# supply.net
KiCad netlist of a schematic drawn in Altium Designer
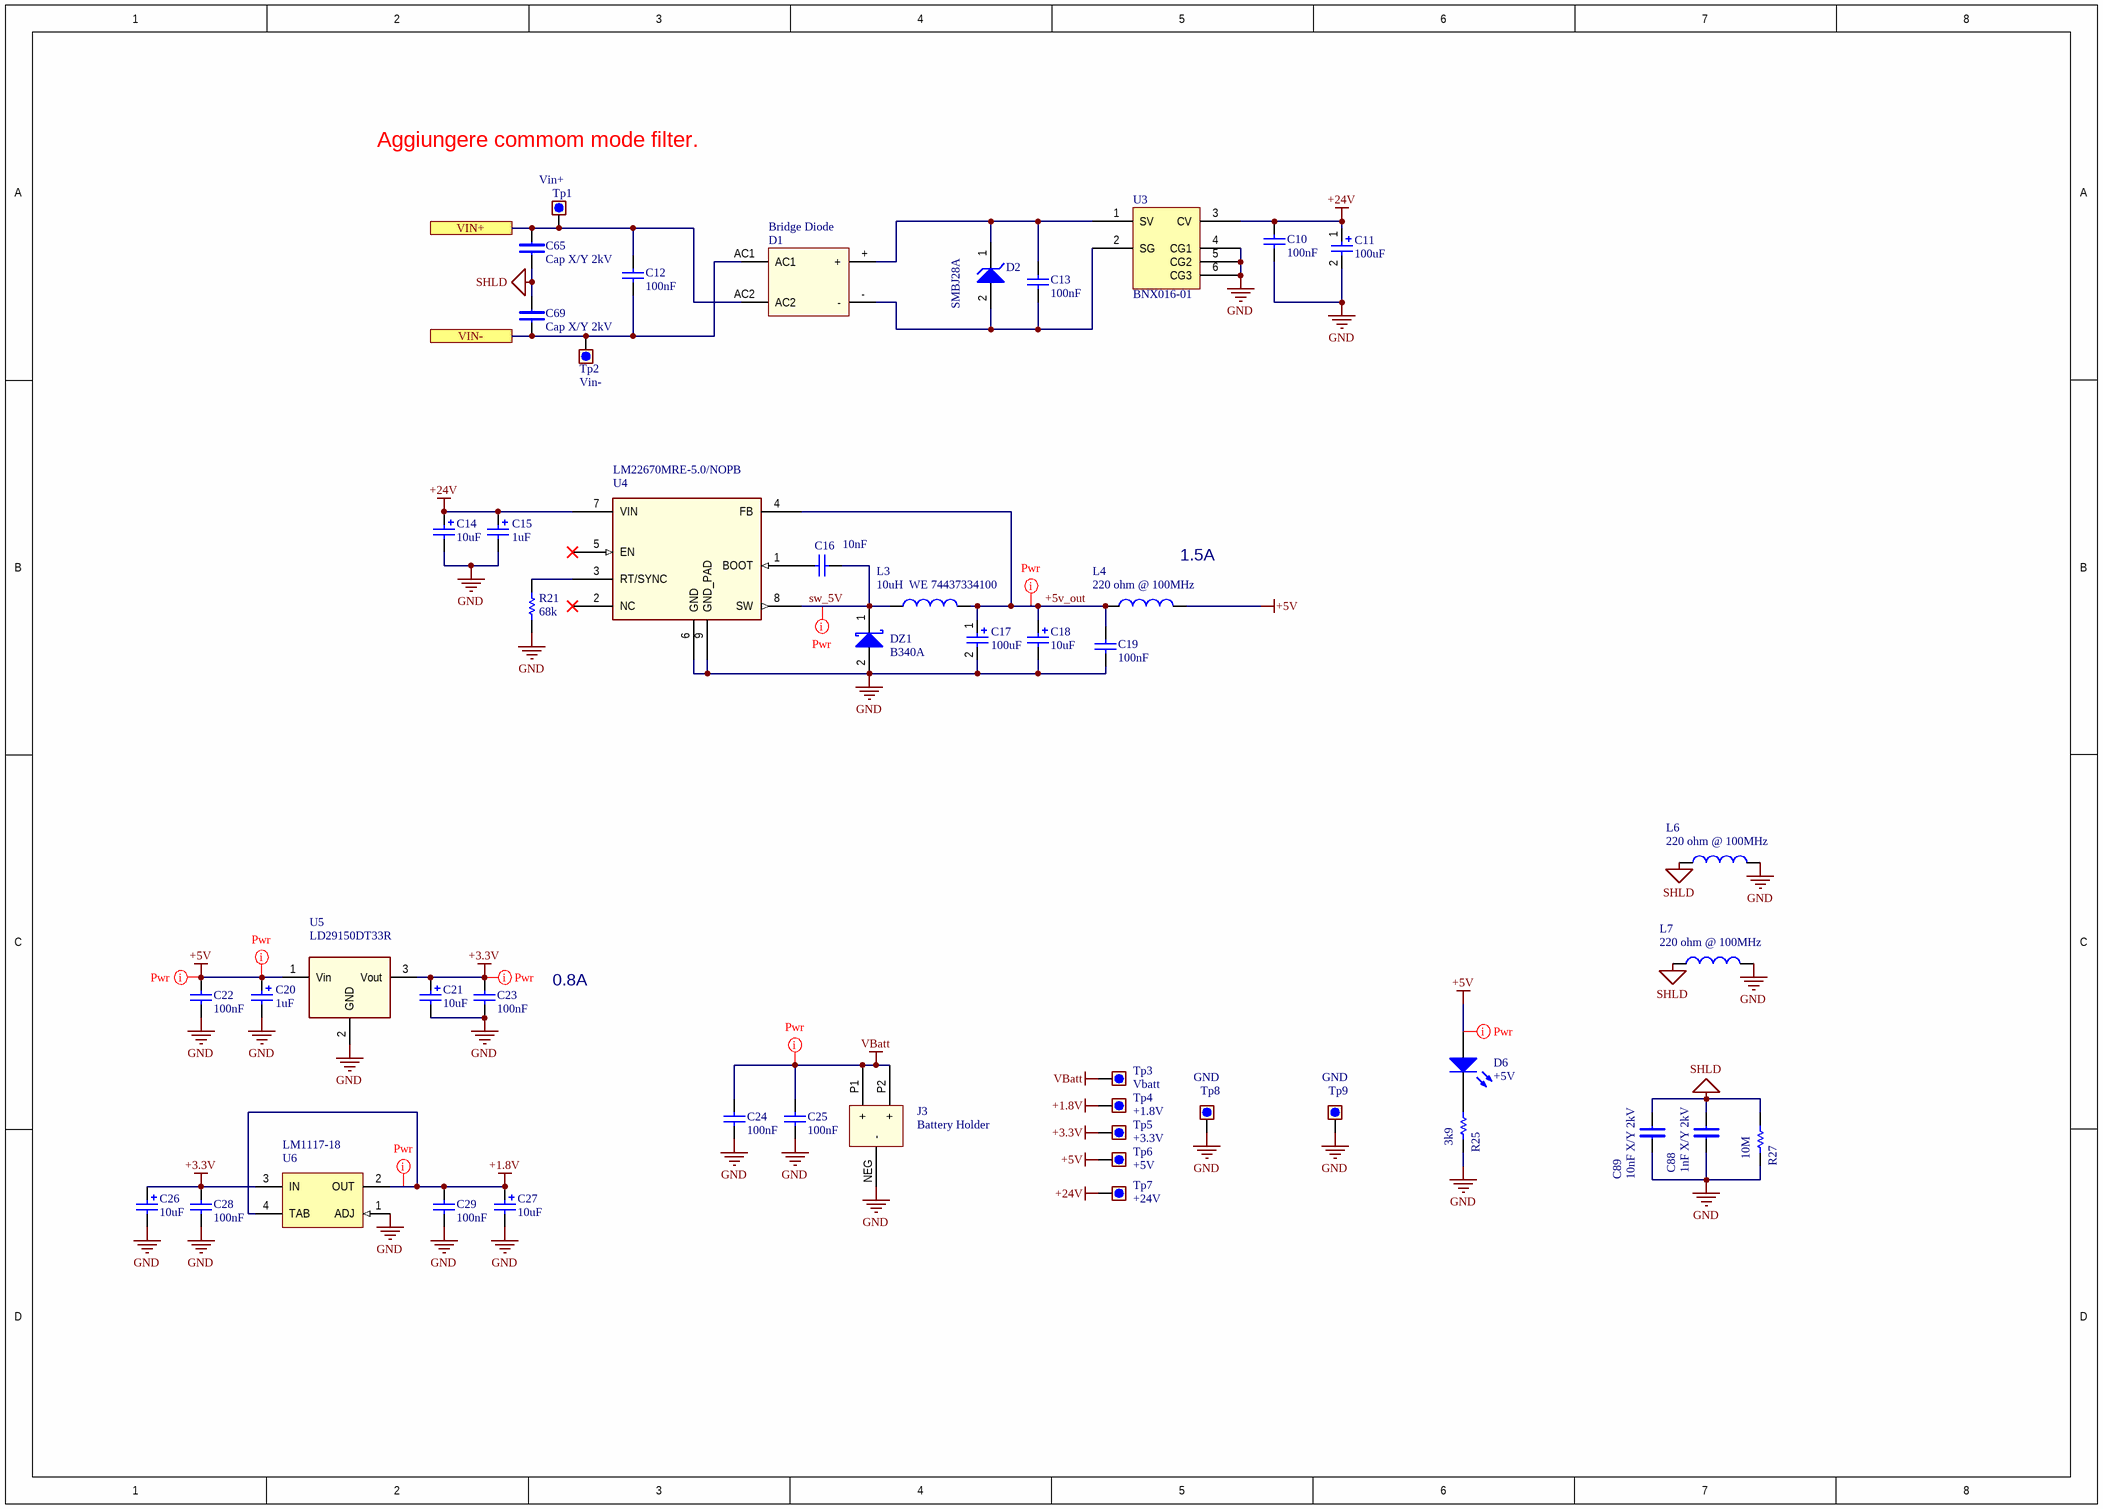
[diagram p0: supply.SchDoc]

(export (version "E")
  (design (tool "Eeschema 10.0.6"))
  (components
    (comp (ref "C10")
      (value "100nF")
      (footprint "0603_[1608]")
      (description "Ceramic X7R 50V")
      (fields (field (name "PUBLISHER") "Altium Limited"))
      (libsource (lib "DEVELER_Library") (part "Cap"))
    )
    (comp (ref "C11")
      (value "100uF")
      (footprint "CAP_6x6_D8_SMD")
      (description "EEEFK1H101P SMT 6x6 35V")
      (fields (field (name "PUBLISHER") "Altium Limited"))
      (libsource (lib "") (part "Cap Pol1_1"))
    )
    (comp (ref "C12")
      (value "100nF")
      (footprint "0603_[1608]")
      (description "Ceramic X7R 50V")
      (fields (field (name "PUBLISHER") "Altium Limited"))
      (libsource (lib "DEVELER_Library") (part "Cap"))
    )
    (comp (ref "C13")
      (value "100nF")
      (footprint "0603_[1608]")
      (description "Ceramic X7R 50V")
      (fields (field (name "PUBLISHER") "Altium Limited"))
      (libsource (lib "DEVELER_Library") (part "Cap"))
    )
    (comp (ref "C14")
      (value "10uF")
      (footprint "1206_[3216]")
      (description "Ceramic X5R 25V")
      (fields (field (name "PUBLISHER") "Altium Limited"))
      (libsource (lib "DEVELER_Library") (part "Cap Pol1"))
    )
    (comp (ref "C15")
      (value "1uF")
      (footprint "0805_[2012]")
      (description "Ceramic X7R 50V")
      (fields (field (name "PUBLISHER") "Altium Limited"))
      (libsource (lib "DEVELER_Library") (part "Cap Pol1"))
    )
    (comp (ref "C16")
      (value "10nF")
      (footprint "0603_[1608]")
      (description "Ceramic X7R 50V")
      (fields (field (name "PUBLISHER") "Altium Limited"))
      (libsource (lib "Miscellaneous Devices") (part "Cap"))
    )
    (comp (ref "C17")
      (value "100uF")
      (footprint "[7343]_CAP_TAN")
      (description "Tantalum 10V (T495D107K010ATE100)")
      (fields (field (name "PUBLISHER") "Altium Limited"))
      (libsource (lib "") (part "Cap Pol1_1"))
    )
    (comp (ref "C18")
      (value "10uF")
      (footprint "1206_[3216]")
      (description "Ceramic X5R 25V")
      (fields (field (name "PUBLISHER") "Altium Limited"))
      (libsource (lib "DEVELER_Library") (part "Cap Pol1"))
    )
    (comp (ref "C19")
      (value "100nF")
      (footprint "0603_[1608]")
      (description "Ceramic X7R 50V")
      (fields (field (name "PUBLISHER") "Altium Limited"))
      (libsource (lib "DEVELER_Library") (part "Cap"))
    )
    (comp (ref "C20")
      (value "1uF")
      (footprint "0805_[2012]")
      (description "Ceramic X7R 50V")
      (fields (field (name "PUBLISHER") "Altium Limited"))
      (libsource (lib "DEVELER_Library") (part "Cap Pol1"))
    )
    (comp (ref "C21")
      (value "10uF")
      (footprint "1206_[3216]")
      (description "Ceramic X5R 25V")
      (fields (field (name "PUBLISHER") "Altium Limited"))
      (libsource (lib "DEVELER_Library") (part "Cap Pol1"))
    )
    (comp (ref "C22")
      (value "100nF")
      (footprint "0603_[1608]")
      (description "Ceramic X7R 50V")
      (fields (field (name "PUBLISHER") "Altium Limited"))
      (libsource (lib "DEVELER_Library") (part "Cap"))
    )
    (comp (ref "C23")
      (value "100nF")
      (footprint "0603_[1608]")
      (description "Ceramic X7R 50V")
      (fields (field (name "PUBLISHER") "Altium Limited"))
      (libsource (lib "DEVELER_Library") (part "Cap"))
    )
    (comp (ref "C24")
      (value "100nF")
      (footprint "0603_[1608]")
      (description "Ceramic X7R 50V")
      (fields (field (name "PUBLISHER") "Altium Limited"))
      (libsource (lib "DEVELER_Library") (part "Cap"))
    )
    (comp (ref "C25")
      (value "100nF")
      (footprint "0603_[1608]")
      (description "Ceramic X7R 50V")
      (fields (field (name "PUBLISHER") "Altium Limited"))
      (libsource (lib "DEVELER_Library") (part "Cap"))
    )
    (comp (ref "C26")
      (value "10uF")
      (footprint "1206_[3216]")
      (description "Ceramic X5R 25V")
      (fields (field (name "PUBLISHER") "Altium Limited"))
      (libsource (lib "DEVELER_Library") (part "Cap Pol1"))
    )
    (comp (ref "C27")
      (value "10uF")
      (footprint "1206_[3216]")
      (description "Ceramic X5R 25V")
      (fields (field (name "PUBLISHER") "Altium Limited"))
      (libsource (lib "DEVELER_Library") (part "Cap Pol1"))
    )
    (comp (ref "C28")
      (value "100nF")
      (footprint "0603_[1608]")
      (description "Ceramic X7R 50V")
      (fields (field (name "PUBLISHER") "Altium Limited"))
      (libsource (lib "DEVELER_Library") (part "Cap"))
    )
    (comp (ref "C29")
      (value "100nF")
      (footprint "0603_[1608]")
      (description "Ceramic X7R 50V")
      (fields (field (name "PUBLISHER") "Altium Limited"))
      (libsource (lib "DEVELER_Library") (part "Cap"))
    )
    (comp (ref "C65")
      (value "Cap X/Y 2kV")
      (footprint "1808_[4520]")
      (description "Ceramic 1nF 1808 250VAC X7R X1/Y1 (Murata GA342DR7GF102KW)")
      (libsource (lib "develer_library") (part "cap_xy"))
    )
    (comp (ref "C69")
      (value "Cap X/Y 2kV")
      (footprint "1808_[4520]")
      (description "Ceramic 1nF 1808 250VAC X7R X1/Y1 (Murata GA342DR7GF102KW)")
      (libsource (lib "develer_library") (part "cap_xy"))
    )
    (comp (ref "C88")
      (value "1nF X/Y 2kV")
      (footprint "1808_[4520]")
      (description "Ceramic 250VAC X7R X1/Y1 (GA342DR7GF102KW)")
      (libsource (lib "develer_library") (part "cap_xy"))
    )
    (comp (ref "C89")
      (value "10nF X/Y 2kV")
      (footprint "2220_[5650]")
      (description "Ceramic 250VAC X7R X1/Y1 (GA355DR7GB103KY02L)")
      (libsource (lib "develer_library") (part "cap_xy"))
    )
    (comp (ref "D1")
      (value "Bridge Diode")
      (footprint "Diode_bridge_smd")
      (description "MBS4 (Farnell cod:4084985)")
      (libsource (lib "DEVELER_Library") (part "Diode_bridge2"))
    )
    (comp (ref "D2")
      (value "SMBJ28A")
      (footprint "DO214AA_K1-A2_SMB")
      (description "TVS Monodirectional")
      (fields (field (name "PUBLISHER") "Altium Limited"))
      (libsource (lib "DEVELER_Library") (part "D Zener"))
    )
    (comp (ref "D6")
      (value "+5V")
      (footprint "0603_[1608]_K2-A1_LED")
      (description "LED Green")
      (fields (field (name "PUBLISHER") "Altium Limited"))
      (libsource (lib "DEVELER_Library") (part "LED0"))
    )
    (comp (ref "DZ1")
      (value "B340A")
      (footprint "DO214AA_K1-A2_SMB")
      (description "Diode Schottky (STPS2L40U)")
      (fields (field (name "PUBLISHER") "Altium Limited"))
      (libsource (lib "Miscellaneous Devices") (part "D Schottky"))
    )
    (comp (ref "J3")
      (value "Battery Holder")
      (footprint "Battery_holder_16mm_thd")
      (description "CR1612/1616/1620/1632 (3013, Keystone)")
      (libsource (lib "DEVELER_Library") (part "Battery_holder_3002"))
    )
    (comp (ref "L3")
      (value "10uH  WE 74437334100")
      (footprint "WE-LHMI_5020")
      (description "SMD Shielded Tiny Power Inductor")
      (fields (field (name "PUBLISHER") "Altium Limited"))
      (libsource (lib "Miscellaneous Devices") (part "Inductor"))
    )
    (comp (ref "L4")
      (value "220 ohm @ 100MHz")
      (footprint "0805_[2012]")
      (description "WE 742792022")
      (libsource (lib "DEVELER_Library") (part "Ferrite Bead"))
    )
    (comp (ref "L6")
      (value "220 ohm @ 100MHz")
      (footprint "0805_[2012]")
      (description "WE 742792022")
      (libsource (lib "DEVELER_Library") (part "Ferrite Bead"))
    )
    (comp (ref "L7")
      (value "220 ohm @ 100MHz")
      (footprint "0805_[2012]")
      (description "WE 742792022")
      (libsource (lib "DEVELER_Library") (part "Ferrite Bead"))
    )
    (comp (ref "R21")
      (value "68k")
      (footprint "0603_[1608]")
      (description "Resistor")
      (libsource (lib "DEVELER_Library") (part "Res1"))
    )
    (comp (ref "R25")
      (value "3k9")
      (footprint "0603_[1608]")
      (description "Resistor")
      (libsource (lib "DEVELER_Library") (part "Res1"))
    )
    (comp (ref "R27")
      (value "10M")
      (footprint "1206_[3216]")
      (description "Resistor")
      (libsource (lib "develer_library") (part "Res1"))
    )
    (comp (ref "Tp1")
      (value "Vin+")
      (footprint "TEST_POINT_THD_D1.8MM")
      (description "Test point")
      (libsource (lib "DEVELER_Library") (part "Test_point"))
    )
    (comp (ref "Tp2")
      (value "Vin-")
      (footprint "TEST_POINT_THD_D1.8MM")
      (description "Test point")
      (libsource (lib "") (part "Test_point_2"))
    )
    (comp (ref "Tp3")
      (value "Vbatt")
      (footprint "TEST_POINT_THD_D1.8MM")
      (description "Test point")
      (libsource (lib "") (part "Test_point_1"))
    )
    (comp (ref "Tp4")
      (value "+1.8V")
      (footprint "TEST_POINT_THD_D1.8MM")
      (description "Test point")
      (libsource (lib "") (part "Test_point_1"))
    )
    (comp (ref "Tp5")
      (value "+3.3V")
      (footprint "TEST_POINT_THD_D1.8MM")
      (description "Test point")
      (libsource (lib "") (part "Test_point_1"))
    )
    (comp (ref "Tp6")
      (value "+5V")
      (footprint "TEST_POINT_THD_D1.8MM")
      (description "Test point")
      (libsource (lib "") (part "Test_point_1"))
    )
    (comp (ref "Tp7")
      (value "+24V")
      (footprint "TEST_POINT_THD_D1.8MM")
      (description "Test point")
      (libsource (lib "") (part "Test_point_1"))
    )
    (comp (ref "Tp8")
      (value "GND")
      (footprint "TEST_POINT_THD_D1.8MM")
      (description "Test point")
      (libsource (lib "DEVELER_Library") (part "Test_point"))
    )
    (comp (ref "Tp9")
      (value "GND")
      (footprint "TEST_POINT_THD_D1.8MM")
      (description "Test point")
      (libsource (lib "DEVELER_Library") (part "Test_point"))
    )
    (comp (ref "U3")
      (value "BNX016-01")
      (footprint "BNX001")
      (description "EMI Filter DC power line")
      (libsource (lib "STR910_SCHLIB") (part "BNX002"))
    )
    (comp (ref "U4")
      (value "LM22670MRE-5.0/NOPB")
      (footprint "SOIC8_PAD")
      (description "Power switch")
      (libsource (lib "DEVELER_Library") (part "LM22670MR-ADJ"))
    )
    (comp (ref "U5")
      (value "LD29150DT33R")
      (footprint "TO-252_D2PAK_LARGEPAD")
      (description "Very Low Drop Linear regulator 3.3V (BA33BC0FP-E2; MIC2940A-3.3WU)")
      (libsource (lib "DEVELER_Library") (part "LD29150DT33R"))
    )
    (comp (ref "U6")
      (value "LM1117-18")
      (footprint "SOT-223")
      (description "LDO, Fixed Vout = 1.8V")
      (fields
        (field (name "PARTNUMBER") "LM317AEMP")
        (field (name "MANUFACTURER") "National Semiconductor")
        (field (name "PUBLISHER") "Altium Limited")
      )
      (libsource (lib "DEVELER_Library") (part "LM317AEMP"))
    )
  )
  (nets
    (net (code "1") (name "+1.8V") (class "Default")
      (node (ref "C27") (pin "1") (pinfunction "1_1") (pintype "passive"))
      (node (ref "C29") (pin "2") (pinfunction "2_2") (pintype "passive"))
      (node (ref "Tp4") (pin "1") (pinfunction "1_1") (pintype "passive"))
      (node (ref "U6") (pin "2") (pinfunction "OUT_2") (pintype "power_in"))
      (node (ref "U6") (pin "4") (pinfunction "TAB_4") (pintype "power_in"))
    )
    (net (code "2") (name "+3.3V") (class "Default")
      (node (ref "C21") (pin "1") (pinfunction "1_1") (pintype "passive"))
      (node (ref "C23") (pin "2") (pinfunction "2_2") (pintype "passive"))
      (node (ref "C26") (pin "1") (pinfunction "1_1") (pintype "passive"))
      (node (ref "C28") (pin "2") (pinfunction "2_2") (pintype "passive"))
      (node (ref "Tp5") (pin "1") (pinfunction "1_1") (pintype "passive"))
      (node (ref "U5") (pin "3") (pinfunction "Vout_3") (pintype "passive"))
      (node (ref "U6") (pin "3") (pinfunction "IN_3") (pintype "power_in"))
    )
    (net (code "3") (name "+5V") (class "Default")
      (node (ref "C20") (pin "1") (pinfunction "1_1") (pintype "passive"))
      (node (ref "C22") (pin "2") (pinfunction "2_2") (pintype "passive"))
      (node (ref "D6") (pin "1") (pinfunction "A_1") (pintype "passive"))
      (node (ref "L4") (pin "1") (pinfunction "1_1") (pintype "passive"))
      (node (ref "Tp6") (pin "1") (pinfunction "1_1") (pintype "passive"))
      (node (ref "U5") (pin "1") (pinfunction "Vin_1") (pintype "passive"))
    )
    (net (code "4") (name "+24V") (class "Default")
      (node (ref "C10") (pin "2") (pinfunction "2_2") (pintype "passive"))
      (node (ref "C11") (pin "1") (pinfunction "1_1") (pintype "passive"))
      (node (ref "C14") (pin "1") (pinfunction "1_1") (pintype "passive"))
      (node (ref "C15") (pin "1") (pinfunction "1_1") (pintype "passive"))
      (node (ref "Tp7") (pin "1") (pinfunction "1_1") (pintype "passive"))
      (node (ref "U3") (pin "3") (pinfunction "CV_3") (pintype "passive"))
      (node (ref "U4") (pin "7") (pinfunction "VIN_7") (pintype "power_in"))
    )
    (net (code "5") (name "/+5v_out") (class "Default")
      (node (ref "C17") (pin "1") (pinfunction "1_1") (pintype "passive"))
      (node (ref "C18") (pin "1") (pinfunction "1_1") (pintype "passive"))
      (node (ref "C19") (pin "2") (pinfunction "2_2") (pintype "passive"))
      (node (ref "L3") (pin "2") (pinfunction "2_2") (pintype "passive"))
      (node (ref "L4") (pin "2") (pinfunction "2_2") (pintype "passive"))
      (node (ref "U4") (pin "4") (pinfunction "FB_4") (pintype "passive"))
    )
    (net (code "6") (name "/VIN+") (class "Default")
      (node (ref "C12") (pin "2") (pinfunction "2_2") (pintype "passive"))
      (node (ref "C65") (pin "1") (pinfunction "1_1") (pintype "passive"))
      (node (ref "D1") (pin "AC2") (pinfunction "AC2_AC2") (pintype "passive"))
      (node (ref "Tp1") (pin "1") (pinfunction "1_1") (pintype "passive"))
    )
    (net (code "7") (name "/VIN-") (class "Default")
      (node (ref "C12") (pin "1") (pinfunction "1_1") (pintype "passive"))
      (node (ref "C69") (pin "2") (pinfunction "2_2") (pintype "passive"))
      (node (ref "D1") (pin "AC1") (pinfunction "AC1_AC1") (pintype "passive"))
      (node (ref "Tp2") (pin "1") (pinfunction "1_1") (pintype "passive"))
    )
    (net (code "8") (name "/sw_5V") (class "Default")
      (node (ref "C16") (pin "2") (pinfunction "2_2") (pintype "passive"))
      (node (ref "DZ1") (pin "1") (pinfunction "K_1") (pintype "passive"))
      (node (ref "L3") (pin "1") (pinfunction "1_1") (pintype "passive"))
      (node (ref "U4") (pin "8") (pinfunction "SW_8") (pintype "output"))
    )
    (net (code "9") (name "GND") (class "Default")
      (node (ref "C10") (pin "1") (pinfunction "1_1") (pintype "passive"))
      (node (ref "C11") (pin "2") (pinfunction "2_2") (pintype "passive"))
      (node (ref "C14") (pin "2") (pinfunction "2_2") (pintype "passive"))
      (node (ref "C15") (pin "2") (pinfunction "2_2") (pintype "passive"))
      (node (ref "C17") (pin "2") (pinfunction "2_2") (pintype "passive"))
      (node (ref "C18") (pin "2") (pinfunction "2_2") (pintype "passive"))
      (node (ref "C19") (pin "1") (pinfunction "1_1") (pintype "passive"))
      (node (ref "C20") (pin "2") (pinfunction "2_2") (pintype "passive"))
      (node (ref "C21") (pin "2") (pinfunction "2_2") (pintype "passive"))
      (node (ref "C22") (pin "1") (pinfunction "1_1") (pintype "passive"))
      (node (ref "C23") (pin "1") (pinfunction "1_1") (pintype "passive"))
      (node (ref "C24") (pin "1") (pinfunction "1_1") (pintype "passive"))
      (node (ref "C25") (pin "1") (pinfunction "1_1") (pintype "passive"))
      (node (ref "C26") (pin "2") (pinfunction "2_2") (pintype "passive"))
      (node (ref "C27") (pin "2") (pinfunction "2_2") (pintype "passive"))
      (node (ref "C28") (pin "1") (pinfunction "1_1") (pintype "passive"))
      (node (ref "C29") (pin "1") (pinfunction "1_1") (pintype "passive"))
      (node (ref "C88") (pin "2") (pinfunction "2_2") (pintype "passive"))
      (node (ref "C89") (pin "2") (pinfunction "2_2") (pintype "passive"))
      (node (ref "DZ1") (pin "2") (pinfunction "A_2") (pintype "passive"))
      (node (ref "J3") (pin "NEG") (pinfunction "-_NEG") (pintype "passive"))
      (node (ref "L6") (pin "1") (pinfunction "1_1") (pintype "passive"))
      (node (ref "L7") (pin "1") (pinfunction "1_1") (pintype "passive"))
      (node (ref "R21") (pin "1") (pinfunction "1_1") (pintype "passive"))
      (node (ref "R25") (pin "1") (pinfunction "1_1") (pintype "passive"))
      (node (ref "R27") (pin "1") (pinfunction "1_1") (pintype "passive"))
      (node (ref "Tp8") (pin "1") (pinfunction "1_1") (pintype "passive"))
      (node (ref "Tp9") (pin "1") (pinfunction "1_1") (pintype "passive"))
      (node (ref "U3") (pin "4") (pinfunction "CG1_4") (pintype "passive"))
      (node (ref "U3") (pin "5") (pinfunction "CG2_5") (pintype "passive"))
      (node (ref "U3") (pin "6") (pinfunction "CG3_6") (pintype "passive"))
      (node (ref "U4") (pin "6") (pinfunction "GND_6") (pintype "power_in"))
      (node (ref "U4") (pin "9") (pinfunction "GND_PAD_9") (pintype "power_in"))
      (node (ref "U5") (pin "2") (pinfunction "GND_2") (pintype "passive"))
      (node (ref "U6") (pin "1") (pinfunction "ADJ_1") (pintype "input"))
    )
    (net (code "10") (name "Net-(D2-A)") (class "Default")
      (node (ref "C13") (pin "1") (pinfunction "1_1") (pintype "passive"))
      (node (ref "D1") (pin "-") (pinfunction "-_-") (pintype "passive"))
      (node (ref "D2") (pin "2") (pinfunction "A_2") (pintype "passive"))
      (node (ref "U3") (pin "2") (pinfunction "SG_2") (pintype "passive"))
    )
    (net (code "11") (name "Net-(D2-K)") (class "Default")
      (node (ref "C13") (pin "2") (pinfunction "2_2") (pintype "passive"))
      (node (ref "D1") (pin "+") (pinfunction "+_+") (pintype "passive"))
      (node (ref "D2") (pin "1") (pinfunction "K_1") (pintype "passive"))
      (node (ref "U3") (pin "1") (pinfunction "SV_1") (pintype "passive"))
    )
    (net (code "12") (name "Net-(D6-K)") (class "Default")
      (node (ref "D6") (pin "2") (pinfunction "K_2") (pintype "passive"))
      (node (ref "R25") (pin "2") (pinfunction "2_2") (pintype "passive"))
    )
    (net (code "13") (name "Net-(U4-BOOT)") (class "Default")
      (node (ref "C16") (pin "1") (pinfunction "1_1") (pintype "passive"))
      (node (ref "U4") (pin "1") (pinfunction "BOOT_1") (pintype "input"))
    )
    (net (code "14") (name "Net-(U4-RT{slash}SYNC)") (class "Default")
      (node (ref "R21") (pin "2") (pinfunction "2_2") (pintype "passive"))
      (node (ref "U4") (pin "3") (pinfunction "RT/SYNC_3") (pintype "passive"))
    )
    (net (code "15") (name "SHLD") (class "Default")
      (node (ref "C65") (pin "2") (pinfunction "2_2") (pintype "passive"))
      (node (ref "C69") (pin "1") (pinfunction "1_1") (pintype "passive"))
      (node (ref "C88") (pin "1") (pinfunction "1_1") (pintype "passive"))
      (node (ref "C89") (pin "1") (pinfunction "1_1") (pintype "passive"))
      (node (ref "L6") (pin "2") (pinfunction "2_2") (pintype "passive"))
      (node (ref "L7") (pin "2") (pinfunction "2_2") (pintype "passive"))
      (node (ref "R27") (pin "2") (pinfunction "2_2") (pintype "passive"))
    )
    (net (code "16") (name "VBatt") (class "Default")
      (node (ref "C24") (pin "2") (pinfunction "2_2") (pintype "passive"))
      (node (ref "C25") (pin "2") (pinfunction "2_2") (pintype "passive"))
      (node (ref "J3") (pin "P1") (pinfunction "+_P1") (pintype "passive"))
      (node (ref "J3") (pin "P2") (pinfunction "+_P2") (pintype "passive"))
      (node (ref "Tp3") (pin "1") (pinfunction "1_1") (pintype "passive"))
    )
    (net (code "17") (name "unconnected-(U4-EN-Pad5)") (class "Default")
      (node (ref "U4") (pin "5") (pinfunction "EN_5") (pintype "input+no_connect"))
    )
    (net (code "18") (name "unconnected-(U4-NC-Pad2)") (class "Default")
      (node (ref "U4") (pin "2") (pinfunction "NC_2") (pintype "passive+no_connect"))
    )
  )
)
